# Stairs_v5.net
KiCad netlist of a schematic drawn in EAGLE
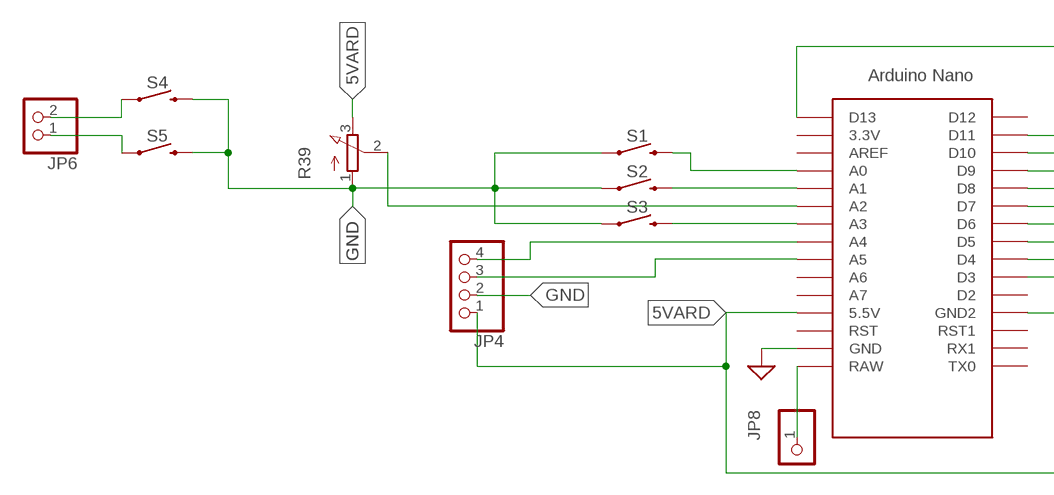
[diagram p0: schematic, sheet 1, part 1 of 2]
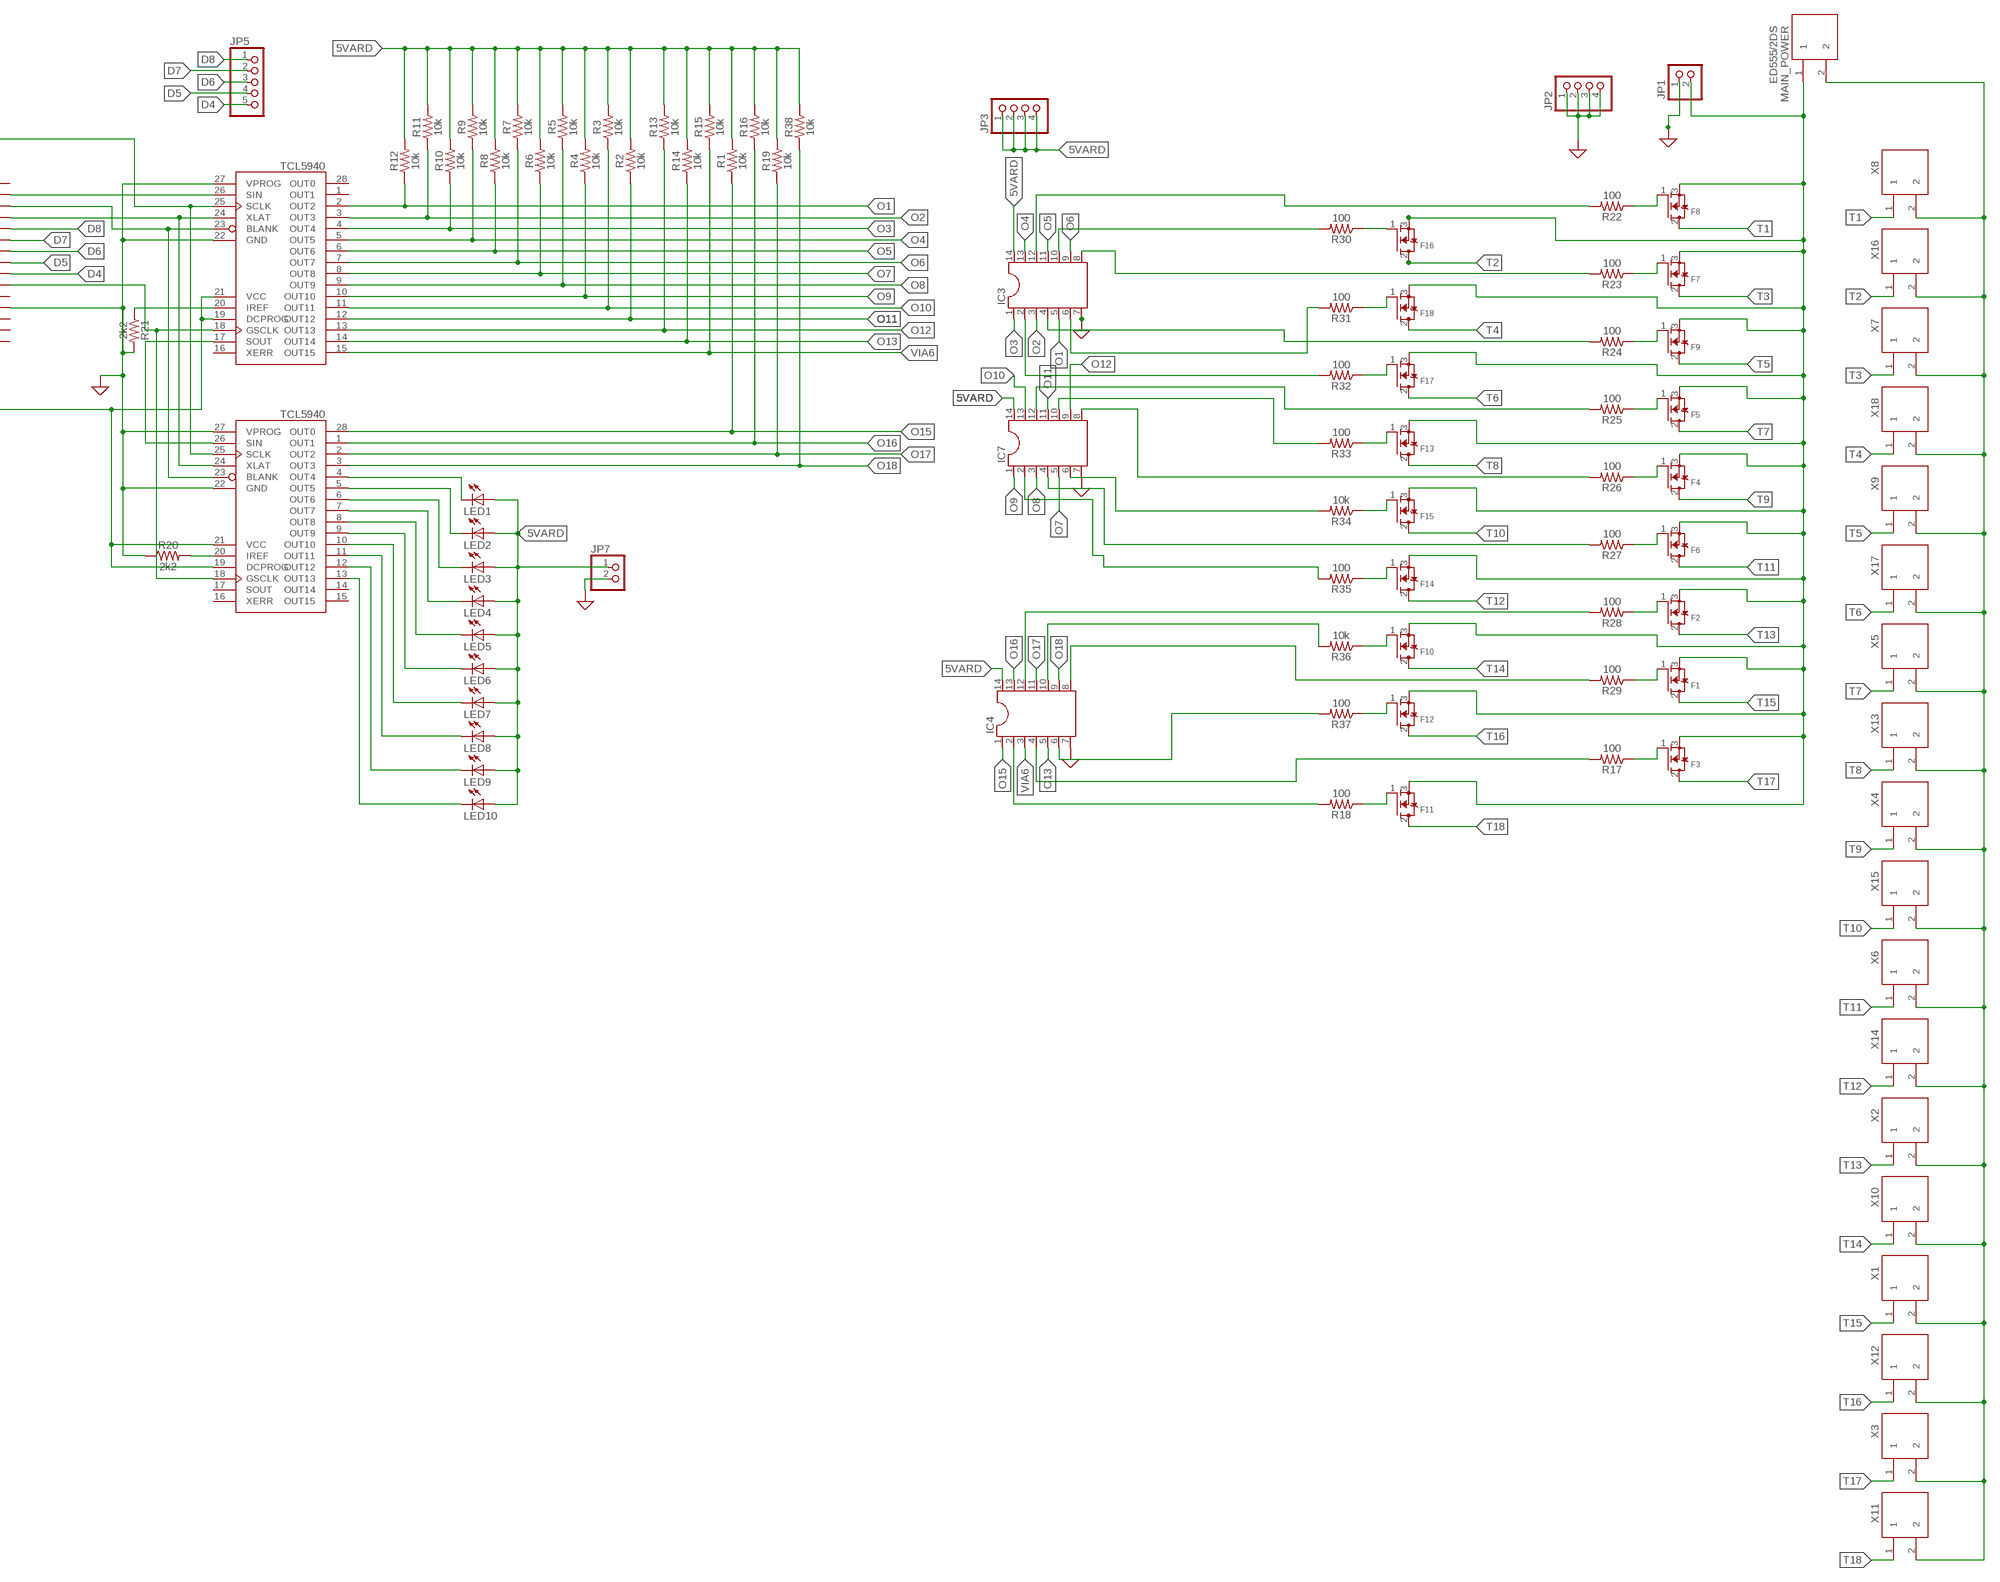
[diagram p1: schematic, sheet 1, part 2 of 2]

(export (version "E")
  (design (tool "Eeschema 10.0.6"))
  (components
    (comp (ref "F1")
      (value "MOSFET-NGDS_TO220V")
      (footprint "eagle-import:TO220V")
      (libsource (lib "eagle-import") (part "MOSFET-NGDS_TO220V"))
    )
    (comp (ref "F2")
      (value "MOSFET-NGDS_TO220V")
      (footprint "eagle-import:TO220V")
      (libsource (lib "eagle-import") (part "MOSFET-NGDS_TO220V"))
    )
    (comp (ref "F3")
      (value "MOSFET-NGDS_TO220V")
      (footprint "eagle-import:TO220V")
      (libsource (lib "eagle-import") (part "MOSFET-NGDS_TO220V"))
    )
    (comp (ref "F4")
      (value "MOSFET-NGDS_TO220V")
      (footprint "eagle-import:TO220V")
      (libsource (lib "eagle-import") (part "MOSFET-NGDS_TO220V"))
    )
    (comp (ref "F5")
      (value "MOSFET-NGDS_TO220V")
      (footprint "eagle-import:TO220V")
      (libsource (lib "eagle-import") (part "MOSFET-NGDS_TO220V"))
    )
    (comp (ref "F6")
      (value "MOSFET-NGDS_TO220V")
      (footprint "eagle-import:TO220V")
      (libsource (lib "eagle-import") (part "MOSFET-NGDS_TO220V"))
    )
    (comp (ref "F7")
      (value "MOSFET-NGDS_TO220V")
      (footprint "eagle-import:TO220V")
      (libsource (lib "eagle-import") (part "MOSFET-NGDS_TO220V"))
    )
    (comp (ref "F8")
      (value "MOSFET-NGDS_TO220V")
      (footprint "eagle-import:TO220V")
      (libsource (lib "eagle-import") (part "MOSFET-NGDS_TO220V"))
    )
    (comp (ref "F9")
      (value "MOSFET-NGDS_TO220V")
      (footprint "eagle-import:TO220V")
      (libsource (lib "eagle-import") (part "MOSFET-NGDS_TO220V"))
    )
    (comp (ref "F10")
      (value "MOSFET-NGDS_TO220V")
      (footprint "eagle-import:TO220V")
      (libsource (lib "eagle-import") (part "MOSFET-NGDS_TO220V"))
    )
    (comp (ref "F11")
      (value "MOSFET-NGDS_TO220V")
      (footprint "eagle-import:TO220V")
      (libsource (lib "eagle-import") (part "MOSFET-NGDS_TO220V"))
    )
    (comp (ref "F12")
      (value "MOSFET-NGDS_TO220V")
      (footprint "eagle-import:TO220V")
      (libsource (lib "eagle-import") (part "MOSFET-NGDS_TO220V"))
    )
    (comp (ref "F13")
      (value "MOSFET-NGDS_TO220V")
      (footprint "eagle-import:TO220V")
      (libsource (lib "eagle-import") (part "MOSFET-NGDS_TO220V"))
    )
    (comp (ref "F14")
      (value "MOSFET-NGDS_TO220V")
      (footprint "eagle-import:TO220V")
      (libsource (lib "eagle-import") (part "MOSFET-NGDS_TO220V"))
    )
    (comp (ref "F15")
      (value "MOSFET-NGDS_TO220V")
      (footprint "eagle-import:TO220V")
      (libsource (lib "eagle-import") (part "MOSFET-NGDS_TO220V"))
    )
    (comp (ref "F16")
      (value "MOSFET-NGDS_TO220V")
      (footprint "eagle-import:TO220V")
      (libsource (lib "eagle-import") (part "MOSFET-NGDS_TO220V"))
    )
    (comp (ref "F17")
      (value "MOSFET-NGDS_TO220V")
      (footprint "eagle-import:TO220V")
      (libsource (lib "eagle-import") (part "MOSFET-NGDS_TO220V"))
    )
    (comp (ref "F18")
      (value "MOSFET-NGDS_TO220V")
      (footprint "eagle-import:TO220V")
      (libsource (lib "eagle-import") (part "MOSFET-NGDS_TO220V"))
    )
    (comp (ref "IC1")
      (value "TCL5940")
      (footprint "eagle-import:DIP28")
      (libsource (lib "eagle-import") (part "TCL5940"))
    )
    (comp (ref "IC2")
      (value "TCL5940")
      (footprint "eagle-import:DIP28")
      (libsource (lib "eagle-import") (part "TCL5940"))
    )
    (comp (ref "IC3")
      (value "DIL14S")
      (footprint "eagle-import:SOCKET-14")
      (libsource (lib "eagle-import") (part "DIL14S"))
    )
    (comp (ref "IC4")
      (value "DIL14S")
      (footprint "eagle-import:SOCKET-14")
      (libsource (lib "eagle-import") (part "DIL14S"))
    )
    (comp (ref "IC7")
      (value "DIL14S")
      (footprint "eagle-import:SOCKET-14")
      (libsource (lib "eagle-import") (part "DIL14S"))
    )
    (comp (ref "JP1")
      (value "PINHD-1X2")
      (footprint "eagle-import:1X02")
      (libsource (lib "eagle-import") (part "PINHD-1X2"))
    )
    (comp (ref "JP2")
      (value "PINHD-1X4")
      (footprint "eagle-import:1X04")
      (libsource (lib "eagle-import") (part "PINHD-1X4"))
    )
    (comp (ref "JP3")
      (value "PINHD-1X4")
      (footprint "eagle-import:1X04")
      (libsource (lib "eagle-import") (part "PINHD-1X4"))
    )
    (comp (ref "JP4")
      (value "PINHD-1X4")
      (footprint "eagle-import:1X04")
      (libsource (lib "eagle-import") (part "PINHD-1X4"))
    )
    (comp (ref "JP5")
      (value "PINHD-1X5")
      (footprint "eagle-import:1X05")
      (libsource (lib "eagle-import") (part "PINHD-1X5"))
    )
    (comp (ref "JP6")
      (value "PINHD-1X2")
      (footprint "eagle-import:1X02")
      (libsource (lib "eagle-import") (part "PINHD-1X2"))
    )
    (comp (ref "JP7")
      (value "PINHD-1X2")
      (footprint "eagle-import:1X02")
      (libsource (lib "eagle-import") (part "PINHD-1X2"))
    )
    (comp (ref "JP8")
      (value "PINHD-1X1")
      (footprint "eagle-import:1X01")
      (libsource (lib "eagle-import") (part "PINHD-1X1"))
    )
    (comp (ref "LED1")
      (value "LEDSFH482")
      (footprint "eagle-import:SFH482")
      (libsource (lib "eagle-import") (part "LEDSFH482"))
    )
    (comp (ref "LED2")
      (value "LEDSFH482")
      (footprint "eagle-import:SFH482")
      (libsource (lib "eagle-import") (part "LEDSFH482"))
    )
    (comp (ref "LED3")
      (value "LEDSFH482")
      (footprint "eagle-import:SFH482")
      (libsource (lib "eagle-import") (part "LEDSFH482"))
    )
    (comp (ref "LED4")
      (value "LEDSFH482")
      (footprint "eagle-import:SFH482")
      (libsource (lib "eagle-import") (part "LEDSFH482"))
    )
    (comp (ref "LED5")
      (value "LEDSFH482")
      (footprint "eagle-import:SFH482")
      (libsource (lib "eagle-import") (part "LEDSFH482"))
    )
    (comp (ref "LED6")
      (value "LEDSFH482")
      (footprint "eagle-import:SFH482")
      (libsource (lib "eagle-import") (part "LEDSFH482"))
    )
    (comp (ref "LED7")
      (value "LEDSFH482")
      (footprint "eagle-import:SFH482")
      (libsource (lib "eagle-import") (part "LEDSFH482"))
    )
    (comp (ref "LED8")
      (value "LEDSFH482")
      (footprint "eagle-import:SFH482")
      (libsource (lib "eagle-import") (part "LEDSFH482"))
    )
    (comp (ref "LED9")
      (value "LEDSFH482")
      (footprint "eagle-import:SFH482")
      (libsource (lib "eagle-import") (part "LEDSFH482"))
    )
    (comp (ref "LED10")
      (value "LEDSFH482")
      (footprint "eagle-import:SFH482")
      (libsource (lib "eagle-import") (part "LEDSFH482"))
    )
    (comp (ref "MAIN_POWER")
      (value "ED555/2DS")
      (footprint "eagle-import:ED555_2DS")
      (libsource (lib "eagle-import") (part "ED555/2DS"))
    )
    (comp (ref "R1")
      (value "10k")
      (footprint "eagle-import:AXIAL-0.3-KIT")
      (libsource (lib "eagle-import") (part "10KOHM-HORIZ_KIT-1/4W-1%"))
    )
    (comp (ref "R2")
      (value "10k")
      (footprint "eagle-import:AXIAL-0.3-KIT")
      (libsource (lib "eagle-import") (part "10KOHM-HORIZ_KIT-1/4W-1%"))
    )
    (comp (ref "R3")
      (value "10k")
      (footprint "eagle-import:AXIAL-0.3-KIT")
      (libsource (lib "eagle-import") (part "10KOHM-HORIZ_KIT-1/4W-1%"))
    )
    (comp (ref "R4")
      (value "10k")
      (footprint "eagle-import:AXIAL-0.3-KIT")
      (libsource (lib "eagle-import") (part "10KOHM-HORIZ_KIT-1/4W-1%"))
    )
    (comp (ref "R5")
      (value "10k")
      (footprint "eagle-import:AXIAL-0.3-KIT")
      (libsource (lib "eagle-import") (part "10KOHM-HORIZ_KIT-1/4W-1%"))
    )
    (comp (ref "R6")
      (value "10k")
      (footprint "eagle-import:AXIAL-0.3-KIT")
      (libsource (lib "eagle-import") (part "10KOHM-HORIZ_KIT-1/4W-1%"))
    )
    (comp (ref "R7")
      (value "10k")
      (footprint "eagle-import:AXIAL-0.3-KIT")
      (libsource (lib "eagle-import") (part "10KOHM-HORIZ_KIT-1/4W-1%"))
    )
    (comp (ref "R8")
      (value "10k")
      (footprint "eagle-import:AXIAL-0.3-KIT")
      (libsource (lib "eagle-import") (part "10KOHM-HORIZ_KIT-1/4W-1%"))
    )
    (comp (ref "R9")
      (value "10k")
      (footprint "eagle-import:AXIAL-0.3-KIT")
      (libsource (lib "eagle-import") (part "10KOHM-HORIZ_KIT-1/4W-1%"))
    )
    (comp (ref "R10")
      (value "10k")
      (footprint "eagle-import:AXIAL-0.3-KIT")
      (libsource (lib "eagle-import") (part "10KOHM-HORIZ_KIT-1/4W-1%"))
    )
    (comp (ref "R11")
      (value "10k")
      (footprint "eagle-import:AXIAL-0.3-KIT")
      (libsource (lib "eagle-import") (part "10KOHM-HORIZ_KIT-1/4W-1%"))
    )
    (comp (ref "R12")
      (value "10k")
      (footprint "eagle-import:AXIAL-0.3-KIT")
      (libsource (lib "eagle-import") (part "10KOHM-HORIZ_KIT-1/4W-1%"))
    )
    (comp (ref "R13")
      (value "10k")
      (footprint "eagle-import:AXIAL-0.3-KIT")
      (libsource (lib "eagle-import") (part "10KOHM-HORIZ_KIT-1/4W-1%"))
    )
    (comp (ref "R14")
      (value "10k")
      (footprint "eagle-import:AXIAL-0.3-KIT")
      (libsource (lib "eagle-import") (part "10KOHM-HORIZ_KIT-1/4W-1%"))
    )
    (comp (ref "R15")
      (value "10k")
      (footprint "eagle-import:AXIAL-0.3-KIT")
      (libsource (lib "eagle-import") (part "10KOHM-HORIZ_KIT-1/4W-1%"))
    )
    (comp (ref "R16")
      (value "10k")
      (footprint "eagle-import:AXIAL-0.3-KIT")
      (libsource (lib "eagle-import") (part "10KOHM-HORIZ_KIT-1/4W-1%"))
    )
    (comp (ref "R17")
      (value "100")
      (footprint "eagle-import:AXIAL-0.3-KIT")
      (libsource (lib "eagle-import") (part "10KOHM-HORIZ_KIT-1/4W-1%"))
    )
    (comp (ref "R18")
      (value "100")
      (footprint "eagle-import:AXIAL-0.3-KIT")
      (libsource (lib "eagle-import") (part "10KOHM-HORIZ_KIT-1/4W-1%"))
    )
    (comp (ref "R19")
      (value "10k")
      (footprint "eagle-import:AXIAL-0.3-KIT")
      (libsource (lib "eagle-import") (part "10KOHM-HORIZ_KIT-1/4W-1%"))
    )
    (comp (ref "R20")
      (value "2k2")
      (footprint "eagle-import:AXIAL-0.3-KIT")
      (libsource (lib "eagle-import") (part "10KOHM-HORIZ_KIT-1/4W-1%"))
    )
    (comp (ref "R21")
      (value "2k2")
      (footprint "eagle-import:AXIAL-0.3-KIT")
      (libsource (lib "eagle-import") (part "10KOHM-HORIZ_KIT-1/4W-1%"))
    )
    (comp (ref "R22")
      (value "100")
      (footprint "eagle-import:AXIAL-0.3-KIT")
      (libsource (lib "eagle-import") (part "10KOHM-HORIZ_KIT-1/4W-1%"))
    )
    (comp (ref "R23")
      (value "100")
      (footprint "eagle-import:AXIAL-0.3-KIT")
      (libsource (lib "eagle-import") (part "10KOHM-HORIZ_KIT-1/4W-1%"))
    )
    (comp (ref "R24")
      (value "100")
      (footprint "eagle-import:AXIAL-0.3-KIT")
      (libsource (lib "eagle-import") (part "10KOHM-HORIZ_KIT-1/4W-1%"))
    )
    (comp (ref "R25")
      (value "100")
      (footprint "eagle-import:AXIAL-0.3-KIT")
      (libsource (lib "eagle-import") (part "10KOHM-HORIZ_KIT-1/4W-1%"))
    )
    (comp (ref "R26")
      (value "100")
      (footprint "eagle-import:AXIAL-0.3-KIT")
      (libsource (lib "eagle-import") (part "10KOHM-HORIZ_KIT-1/4W-1%"))
    )
    (comp (ref "R27")
      (value "100")
      (footprint "eagle-import:AXIAL-0.3-KIT")
      (libsource (lib "eagle-import") (part "10KOHM-HORIZ_KIT-1/4W-1%"))
    )
    (comp (ref "R28")
      (value "100")
      (footprint "eagle-import:AXIAL-0.3-KIT")
      (libsource (lib "eagle-import") (part "10KOHM-HORIZ_KIT-1/4W-1%"))
    )
    (comp (ref "R29")
      (value "100")
      (footprint "eagle-import:AXIAL-0.3-KIT")
      (libsource (lib "eagle-import") (part "10KOHM-HORIZ_KIT-1/4W-1%"))
    )
    (comp (ref "R30")
      (value "100")
      (footprint "eagle-import:AXIAL-0.3-KIT")
      (libsource (lib "eagle-import") (part "10KOHM-HORIZ_KIT-1/4W-1%"))
    )
    (comp (ref "R31")
      (value "100")
      (footprint "eagle-import:AXIAL-0.3-KIT")
      (libsource (lib "eagle-import") (part "10KOHM-HORIZ_KIT-1/4W-1%"))
    )
    (comp (ref "R32")
      (value "100")
      (footprint "eagle-import:AXIAL-0.3-KIT")
      (libsource (lib "eagle-import") (part "10KOHM-HORIZ_KIT-1/4W-1%"))
    )
    (comp (ref "R33")
      (value "100")
      (footprint "eagle-import:AXIAL-0.3-KIT")
      (libsource (lib "eagle-import") (part "10KOHM-HORIZ_KIT-1/4W-1%"))
    )
    (comp (ref "R34")
      (value "10k")
      (footprint "eagle-import:AXIAL-0.3-KIT")
      (libsource (lib "eagle-import") (part "10KOHM-HORIZ_KIT-1/4W-1%"))
    )
    (comp (ref "R35")
      (value "100")
      (footprint "eagle-import:AXIAL-0.3-KIT")
      (libsource (lib "eagle-import") (part "10KOHM-HORIZ_KIT-1/4W-1%"))
    )
    (comp (ref "R36")
      (value "10k")
      (footprint "eagle-import:AXIAL-0.3-KIT")
      (libsource (lib "eagle-import") (part "10KOHM-HORIZ_KIT-1/4W-1%"))
    )
    (comp (ref "R37")
      (value "100")
      (footprint "eagle-import:AXIAL-0.3-KIT")
      (libsource (lib "eagle-import") (part "10KOHM-HORIZ_KIT-1/4W-1%"))
    )
    (comp (ref "R38")
      (value "10k")
      (footprint "eagle-import:AXIAL-0.3-KIT")
      (libsource (lib "eagle-import") (part "10KOHM-HORIZ_KIT-1/4W-1%"))
    )
    (comp (ref "R39")
      (value "3RP/1610N")
      (footprint "eagle-import:3RP_1610N")
      (libsource (lib "eagle-import") (part "3RP/1610N"))
    )
    (comp (ref "S1")
      (value "MOMENTARY-SWITCH-SPST-PTH-6.0MM")
      (footprint "eagle-import:TACTILE_SWITCH_PTH_6.0MM")
      (libsource (lib "eagle-import") (part "MOMENTARY-SWITCH-SPST-PTH-6.0MM"))
    )
    (comp (ref "S2")
      (value "MOMENTARY-SWITCH-SPST-PTH-6.0MM")
      (footprint "eagle-import:TACTILE_SWITCH_PTH_6.0MM")
      (libsource (lib "eagle-import") (part "MOMENTARY-SWITCH-SPST-PTH-6.0MM"))
    )
    (comp (ref "S3")
      (value "MOMENTARY-SWITCH-SPST-PTH-6.0MM")
      (footprint "eagle-import:TACTILE_SWITCH_PTH_6.0MM")
      (libsource (lib "eagle-import") (part "MOMENTARY-SWITCH-SPST-PTH-6.0MM"))
    )
    (comp (ref "S4")
      (value "MOMENTARY-SWITCH-SPST-PTH-6.0MM")
      (footprint "eagle-import:TACTILE_SWITCH_PTH_6.0MM")
      (libsource (lib "eagle-import") (part "MOMENTARY-SWITCH-SPST-PTH-6.0MM"))
    )
    (comp (ref "S5")
      (value "MOMENTARY-SWITCH-SPST-PTH-6.0MM")
      (footprint "eagle-import:TACTILE_SWITCH_PTH_6.0MM")
      (libsource (lib "eagle-import") (part "MOMENTARY-SWITCH-SPST-PTH-6.0MM"))
    )
    (comp (ref "U$1")
      (value "NANO")
      (footprint "eagle-import:NANO")
      (libsource (lib "eagle-import") (part "NANO"))
    )
    (comp (ref "X1")
      (value "ED555/2DS")
      (footprint "eagle-import:ED555_2DS")
      (libsource (lib "eagle-import") (part "ED555/2DS"))
    )
    (comp (ref "X2")
      (value "ED555/2DS")
      (footprint "eagle-import:ED555_2DS")
      (libsource (lib "eagle-import") (part "ED555/2DS"))
    )
    (comp (ref "X3")
      (value "ED555/2DS")
      (footprint "eagle-import:ED555_2DS")
      (libsource (lib "eagle-import") (part "ED555/2DS"))
    )
    (comp (ref "X4")
      (value "ED555/2DS")
      (footprint "eagle-import:ED555_2DS")
      (libsource (lib "eagle-import") (part "ED555/2DS"))
    )
    (comp (ref "X5")
      (value "ED555/2DS")
      (footprint "eagle-import:ED555_2DS")
      (libsource (lib "eagle-import") (part "ED555/2DS"))
    )
    (comp (ref "X6")
      (value "ED555/2DS")
      (footprint "eagle-import:ED555_2DS")
      (libsource (lib "eagle-import") (part "ED555/2DS"))
    )
    (comp (ref "X7")
      (value "ED555/2DS")
      (footprint "eagle-import:ED555_2DS")
      (libsource (lib "eagle-import") (part "ED555/2DS"))
    )
    (comp (ref "X8")
      (value "ED555/2DS")
      (footprint "eagle-import:ED555_2DS")
      (libsource (lib "eagle-import") (part "ED555/2DS"))
    )
    (comp (ref "X9")
      (value "ED555/2DS")
      (footprint "eagle-import:ED555_2DS")
      (libsource (lib "eagle-import") (part "ED555/2DS"))
    )
    (comp (ref "X10")
      (value "ED555/2DS")
      (footprint "eagle-import:ED555_2DS")
      (libsource (lib "eagle-import") (part "ED555/2DS"))
    )
    (comp (ref "X11")
      (value "ED555/2DS")
      (footprint "eagle-import:ED555_2DS")
      (libsource (lib "eagle-import") (part "ED555/2DS"))
    )
    (comp (ref "X12")
      (value "ED555/2DS")
      (footprint "eagle-import:ED555_2DS")
      (libsource (lib "eagle-import") (part "ED555/2DS"))
    )
    (comp (ref "X13")
      (value "ED555/2DS")
      (footprint "eagle-import:ED555_2DS")
      (libsource (lib "eagle-import") (part "ED555/2DS"))
    )
    (comp (ref "X14")
      (value "ED555/2DS")
      (footprint "eagle-import:ED555_2DS")
      (libsource (lib "eagle-import") (part "ED555/2DS"))
    )
    (comp (ref "X15")
      (value "ED555/2DS")
      (footprint "eagle-import:ED555_2DS")
      (libsource (lib "eagle-import") (part "ED555/2DS"))
    )
    (comp (ref "X16")
      (value "ED555/2DS")
      (footprint "eagle-import:ED555_2DS")
      (libsource (lib "eagle-import") (part "ED555/2DS"))
    )
    (comp (ref "X17")
      (value "ED555/2DS")
      (footprint "eagle-import:ED555_2DS")
      (libsource (lib "eagle-import") (part "ED555/2DS"))
    )
    (comp (ref "X18")
      (value "ED555/2DS")
      (footprint "eagle-import:ED555_2DS")
      (libsource (lib "eagle-import") (part "ED555/2DS"))
    )
  )
  (nets
    (net (code "1") (name "5VARD") (class "Default")
      (node (ref "IC1") (pin "19") (pinfunction "DCPROG_19") (pintype "input"))
      (node (ref "IC1") (pin "21") (pinfunction "VCC_21") (pintype "power_in"))
      (node (ref "IC2") (pin "19") (pinfunction "DCPROG_19") (pintype "input"))
      (node (ref "IC2") (pin "21") (pinfunction "VCC_21") (pintype "power_in"))
      (node (ref "IC3") (pin "14") (pinfunction "14_14") (pintype "passive"))
      (node (ref "IC4") (pin "14") (pinfunction "14_14") (pintype "passive"))
      (node (ref "IC7") (pin "14") (pinfunction "14_14") (pintype "passive"))
      (node (ref "JP3") (pin "1") (pinfunction "1_1") (pintype "passive"))
      (node (ref "JP3") (pin "2") (pinfunction "2_2") (pintype "passive"))
      (node (ref "JP3") (pin "3") (pinfunction "3_3") (pintype "passive"))
      (node (ref "JP3") (pin "4") (pinfunction "4_4") (pintype "passive"))
      (node (ref "JP4") (pin "1") (pinfunction "1_1") (pintype "passive"))
      (node (ref "JP7") (pin "1") (pinfunction "1_1") (pintype "passive"))
      (node (ref "LED1") (pin "A") (pinfunction "A_A") (pintype "passive"))
      (node (ref "LED10") (pin "A") (pinfunction "A_A") (pintype "passive"))
      (node (ref "LED2") (pin "A") (pinfunction "A_A") (pintype "passive"))
      (node (ref "LED3") (pin "A") (pinfunction "A_A") (pintype "passive"))
      (node (ref "LED4") (pin "A") (pinfunction "A_A") (pintype "passive"))
      (node (ref "LED5") (pin "A") (pinfunction "A_A") (pintype "passive"))
      (node (ref "LED6") (pin "A") (pinfunction "A_A") (pintype "passive"))
      (node (ref "LED7") (pin "A") (pinfunction "A_A") (pintype "passive"))
      (node (ref "LED8") (pin "A") (pinfunction "A_A") (pintype "passive"))
      (node (ref "LED9") (pin "A") (pinfunction "A_A") (pintype "passive"))
      (node (ref "R1") (pin "P$2") (pinfunction "2_P$2") (pintype "passive"))
      (node (ref "R10") (pin "P$2") (pinfunction "2_P$2") (pintype "passive"))
      (node (ref "R11") (pin "P$2") (pinfunction "2_P$2") (pintype "passive"))
      (node (ref "R12") (pin "P$2") (pinfunction "2_P$2") (pintype "passive"))
      (node (ref "R13") (pin "P$2") (pinfunction "2_P$2") (pintype "passive"))
      (node (ref "R14") (pin "P$2") (pinfunction "2_P$2") (pintype "passive"))
      (node (ref "R15") (pin "P$2") (pinfunction "2_P$2") (pintype "passive"))
      (node (ref "R16") (pin "P$2") (pinfunction "2_P$2") (pintype "passive"))
      (node (ref "R19") (pin "P$2") (pinfunction "2_P$2") (pintype "passive"))
      (node (ref "R2") (pin "P$2") (pinfunction "2_P$2") (pintype "passive"))
      (node (ref "R3") (pin "P$2") (pinfunction "2_P$2") (pintype "passive"))
      (node (ref "R38") (pin "P$2") (pinfunction "2_P$2") (pintype "passive"))
      (node (ref "R39") (pin "3") (pinfunction "E_3") (pintype "passive"))
      (node (ref "R4") (pin "P$2") (pinfunction "2_P$2") (pintype "passive"))
      (node (ref "R5") (pin "P$2") (pinfunction "2_P$2") (pintype "passive"))
      (node (ref "R6") (pin "P$2") (pinfunction "2_P$2") (pintype "passive"))
      (node (ref "R7") (pin "P$2") (pinfunction "2_P$2") (pintype "passive"))
      (node (ref "R8") (pin "P$2") (pinfunction "2_P$2") (pintype "passive"))
      (node (ref "R9") (pin "P$2") (pinfunction "2_P$2") (pintype "passive"))
      (node (ref "U$1") (pin "5V") (pinfunction "5.5V_5V") (pintype "bidirectional"))
    )
    (net (code "2") (name "D4") (class "Default")
      (node (ref "JP5") (pin "5") (pinfunction "5_5") (pintype "passive"))
      (node (ref "U$1") (pin "D4") (pinfunction "D4_D4") (pintype "bidirectional"))
    )
    (net (code "3") (name "D5") (class "Default")
      (node (ref "JP5") (pin "4") (pinfunction "4_4") (pintype "passive"))
      (node (ref "U$1") (pin "D5") (pinfunction "D5_D5") (pintype "bidirectional"))
    )
    (net (code "4") (name "D6") (class "Default")
      (node (ref "JP5") (pin "3") (pinfunction "3_3") (pintype "passive"))
      (node (ref "U$1") (pin "D6") (pinfunction "D6_D6") (pintype "bidirectional"))
    )
    (net (code "5") (name "D7") (class "Default")
      (node (ref "JP5") (pin "2") (pinfunction "2_2") (pintype "passive"))
      (node (ref "U$1") (pin "D7") (pinfunction "D7_D7") (pintype "bidirectional"))
    )
    (net (code "6") (name "D8") (class "Default")
      (node (ref "JP5") (pin "1") (pinfunction "1_1") (pintype "passive"))
      (node (ref "U$1") (pin "D8") (pinfunction "D8_D8") (pintype "bidirectional"))
    )
    (net (code "7") (name "GND") (class "Default")
      (node (ref "IC1") (pin "22") (pinfunction "GND_22") (pintype "power_in"))
      (node (ref "IC1") (pin "27") (pinfunction "VPROG_27") (pintype "bidirectional"))
      (node (ref "IC2") (pin "22") (pinfunction "GND_22") (pintype "power_in"))
      (node (ref "IC2") (pin "27") (pinfunction "VPROG_27") (pintype "bidirectional"))
      (node (ref "IC3") (pin "7") (pinfunction "7_7") (pintype "passive"))
      (node (ref "IC4") (pin "7") (pinfunction "7_7") (pintype "passive"))
      (node (ref "IC7") (pin "7") (pinfunction "7_7") (pintype "passive"))
      (node (ref "JP1") (pin "1") (pinfunction "1_1") (pintype "passive"))
      (node (ref "JP2") (pin "1") (pinfunction "1_1") (pintype "passive"))
      (node (ref "JP2") (pin "2") (pinfunction "2_2") (pintype "passive"))
      (node (ref "JP2") (pin "3") (pinfunction "3_3") (pintype "passive"))
      (node (ref "JP2") (pin "4") (pinfunction "4_4") (pintype "passive"))
      (node (ref "JP4") (pin "2") (pinfunction "2_2") (pintype "passive"))
      (node (ref "JP7") (pin "2") (pinfunction "2_2") (pintype "passive"))
      (node (ref "R20") (pin "P$1") (pinfunction "1_P$1") (pintype "passive"))
      (node (ref "R21") (pin "P$2") (pinfunction "2_P$2") (pintype "passive"))
      (node (ref "R39") (pin "1") (pinfunction "A_1") (pintype "passive"))
      (node (ref "S1") (pin "1") (pinfunction "1_1") (pintype "passive"))
      (node (ref "S2") (pin "1") (pinfunction "1_1") (pintype "passive"))
      (node (ref "S3") (pin "1") (pinfunction "1_1") (pintype "passive"))
      (node (ref "S4") (pin "3") (pinfunction "2_3") (pintype "passive"))
      (node (ref "S5") (pin "3") (pinfunction "2_3") (pintype "passive"))
      (node (ref "U$1") (pin "GND") (pinfunction "GND_GND") (pintype "bidirectional"))
      (node (ref "U$1") (pin "GND1") (pinfunction "GND2_GND1") (pintype "bidirectional"))
    )
    (net (code "8") (name "Net-(F1-G)") (class "Default")
      (node (ref "F1") (pin "1") (pinfunction "G_1") (pintype "bidirectional"))
      (node (ref "R29") (pin "P$1") (pinfunction "1_P$1") (pintype "passive"))
    )
    (net (code "9") (name "Net-(F1-S)") (class "Default")
      (node (ref "F1") (pin "3") (pinfunction "S_3") (pintype "bidirectional"))
      (node (ref "F10") (pin "3") (pinfunction "S_3") (pintype "bidirectional"))
      (node (ref "F11") (pin "3") (pinfunction "S_3") (pintype "bidirectional"))
      (node (ref "F12") (pin "3") (pinfunction "S_3") (pintype "bidirectional"))
      (node (ref "F13") (pin "3") (pinfunction "S_3") (pintype "bidirectional"))
      (node (ref "F14") (pin "3") (pinfunction "S_3") (pintype "bidirectional"))
      (node (ref "F15") (pin "3") (pinfunction "S_3") (pintype "bidirectional"))
      (node (ref "F16") (pin "3") (pinfunction "S_3") (pintype "bidirectional"))
      (node (ref "F17") (pin "3") (pinfunction "S_3") (pintype "bidirectional"))
      (node (ref "F18") (pin "3") (pinfunction "S_3") (pintype "bidirectional"))
      (node (ref "F2") (pin "3") (pinfunction "S_3") (pintype "bidirectional"))
      (node (ref "F3") (pin "3") (pinfunction "S_3") (pintype "bidirectional"))
      (node (ref "F4") (pin "3") (pinfunction "S_3") (pintype "bidirectional"))
      (node (ref "F5") (pin "3") (pinfunction "S_3") (pintype "bidirectional"))
      (node (ref "F6") (pin "3") (pinfunction "S_3") (pintype "bidirectional"))
      (node (ref "F7") (pin "3") (pinfunction "S_3") (pintype "bidirectional"))
      (node (ref "F8") (pin "3") (pinfunction "S_3") (pintype "bidirectional"))
      (node (ref "F9") (pin "3") (pinfunction "S_3") (pintype "bidirectional"))
      (node (ref "JP1") (pin "2") (pinfunction "2_2") (pintype "passive"))
      (node (ref "MAIN_POWER") (pin "1") (pinfunction "1_1") (pintype "bidirectional"))
    )
    (net (code "10") (name "Net-(F2-G)") (class "Default")
      (node (ref "F2") (pin "1") (pinfunction "G_1") (pintype "bidirectional"))
      (node (ref "R28") (pin "P$1") (pinfunction "1_P$1") (pintype "passive"))
    )
    (net (code "11") (name "Net-(F3-G)") (class "Default")
      (node (ref "F3") (pin "1") (pinfunction "G_1") (pintype "bidirectional"))
      (node (ref "R17") (pin "P$1") (pinfunction "1_P$1") (pintype "passive"))
    )
    (net (code "12") (name "Net-(F4-G)") (class "Default")
      (node (ref "F4") (pin "1") (pinfunction "G_1") (pintype "bidirectional"))
      (node (ref "R26") (pin "P$1") (pinfunction "1_P$1") (pintype "passive"))
    )
    (net (code "13") (name "Net-(F5-G)") (class "Default")
      (node (ref "F5") (pin "1") (pinfunction "G_1") (pintype "bidirectional"))
      (node (ref "R25") (pin "P$1") (pinfunction "1_P$1") (pintype "passive"))
    )
    (net (code "14") (name "Net-(F6-G)") (class "Default")
      (node (ref "F6") (pin "1") (pinfunction "G_1") (pintype "bidirectional"))
      (node (ref "R27") (pin "P$1") (pinfunction "1_P$1") (pintype "passive"))
    )
    (net (code "15") (name "Net-(F7-G)") (class "Default")
      (node (ref "F7") (pin "1") (pinfunction "G_1") (pintype "bidirectional"))
      (node (ref "R23") (pin "P$1") (pinfunction "1_P$1") (pintype "passive"))
    )
    (net (code "16") (name "Net-(F8-G)") (class "Default")
      (node (ref "F8") (pin "1") (pinfunction "G_1") (pintype "bidirectional"))
      (node (ref "R22") (pin "P$1") (pinfunction "1_P$1") (pintype "passive"))
    )
    (net (code "17") (name "Net-(F9-G)") (class "Default")
      (node (ref "F9") (pin "1") (pinfunction "G_1") (pintype "bidirectional"))
      (node (ref "R24") (pin "P$1") (pinfunction "1_P$1") (pintype "passive"))
    )
    (net (code "18") (name "Net-(F10-G)") (class "Default")
      (node (ref "F10") (pin "1") (pinfunction "G_1") (pintype "bidirectional"))
      (node (ref "R36") (pin "P$1") (pinfunction "1_P$1") (pintype "passive"))
    )
    (net (code "19") (name "Net-(F11-G)") (class "Default")
      (node (ref "F11") (pin "1") (pinfunction "G_1") (pintype "bidirectional"))
      (node (ref "R18") (pin "P$1") (pinfunction "1_P$1") (pintype "passive"))
    )
    (net (code "20") (name "Net-(F12-G)") (class "Default")
      (node (ref "F12") (pin "1") (pinfunction "G_1") (pintype "bidirectional"))
      (node (ref "R37") (pin "P$1") (pinfunction "1_P$1") (pintype "passive"))
    )
    (net (code "21") (name "Net-(F13-G)") (class "Default")
      (node (ref "F13") (pin "1") (pinfunction "G_1") (pintype "bidirectional"))
      (node (ref "R33") (pin "P$1") (pinfunction "1_P$1") (pintype "passive"))
    )
    (net (code "22") (name "Net-(F14-G)") (class "Default")
      (node (ref "F14") (pin "1") (pinfunction "G_1") (pintype "bidirectional"))
      (node (ref "R35") (pin "P$1") (pinfunction "1_P$1") (pintype "passive"))
    )
    (net (code "23") (name "Net-(F15-G)") (class "Default")
      (node (ref "F15") (pin "1") (pinfunction "G_1") (pintype "bidirectional"))
      (node (ref "R34") (pin "P$1") (pinfunction "1_P$1") (pintype "passive"))
    )
    (net (code "24") (name "Net-(F16-G)") (class "Default")
      (node (ref "F16") (pin "1") (pinfunction "G_1") (pintype "bidirectional"))
      (node (ref "R30") (pin "P$1") (pinfunction "1_P$1") (pintype "passive"))
    )
    (net (code "25") (name "Net-(F17-G)") (class "Default")
      (node (ref "F17") (pin "1") (pinfunction "G_1") (pintype "bidirectional"))
      (node (ref "R32") (pin "P$1") (pinfunction "1_P$1") (pintype "passive"))
    )
    (net (code "26") (name "Net-(F18-G)") (class "Default")
      (node (ref "F18") (pin "1") (pinfunction "G_1") (pintype "bidirectional"))
      (node (ref "R31") (pin "P$1") (pinfunction "1_P$1") (pintype "passive"))
    )
    (net (code "27") (name "Net-(IC1-BLANK)") (class "Default")
      (node (ref "IC1") (pin "23") (pinfunction "BLANK_23") (pintype "input"))
      (node (ref "IC2") (pin "23") (pinfunction "BLANK_23") (pintype "input"))
      (node (ref "U$1") (pin "D10") (pinfunction "D10_D10") (pintype "bidirectional"))
    )
    (net (code "28") (name "Net-(IC1-GSCLK)") (class "Default")
      (node (ref "IC1") (pin "18") (pinfunction "GSCLK_18") (pintype "input"))
      (node (ref "IC2") (pin "18") (pinfunction "GSCLK_18") (pintype "input"))
      (node (ref "U$1") (pin "D3") (pinfunction "D3_D3") (pintype "bidirectional"))
    )
    (net (code "29") (name "Net-(IC1-IREF)") (class "Default")
      (node (ref "IC1") (pin "20") (pinfunction "IREF_20") (pintype "input"))
      (node (ref "R21") (pin "P$1") (pinfunction "1_P$1") (pintype "passive"))
    )
    (net (code "30") (name "Net-(IC1-SCLK)") (class "Default")
      (node (ref "IC1") (pin "25") (pinfunction "SCLK_25") (pintype "input"))
      (node (ref "IC2") (pin "25") (pinfunction "SCLK_25") (pintype "input"))
      (node (ref "U$1") (pin "D13") (pinfunction "D13_D13") (pintype "bidirectional"))
    )
    (net (code "31") (name "Net-(IC1-SIN)") (class "Default")
      (node (ref "IC1") (pin "26") (pinfunction "SIN_26") (pintype "input"))
      (node (ref "U$1") (pin "D11") (pinfunction "D11_D11") (pintype "bidirectional"))
    )
    (net (code "32") (name "Net-(IC1-SOUT)") (class "Default")
      (node (ref "IC1") (pin "17") (pinfunction "SOUT_17") (pintype "output"))
      (node (ref "IC2") (pin "26") (pinfunction "SIN_26") (pintype "input"))
    )
    (net (code "33") (name "Net-(IC1-XLAT)") (class "Default")
      (node (ref "IC1") (pin "24") (pinfunction "XLAT_24") (pintype "input"))
      (node (ref "IC2") (pin "24") (pinfunction "XLAT_24") (pintype "input"))
      (node (ref "U$1") (pin "D9") (pinfunction "D9_D9") (pintype "bidirectional"))
    )
    (net (code "34") (name "Net-(IC2-IREF)") (class "Default")
      (node (ref "IC2") (pin "20") (pinfunction "IREF_20") (pintype "input"))
      (node (ref "R20") (pin "P$2") (pinfunction "2_P$2") (pintype "passive"))
    )
    (net (code "35") (name "Net-(IC2-OUT4)") (class "Default")
      (node (ref "IC2") (pin "4") (pinfunction "OUT4_4") (pintype "output"))
      (node (ref "LED1") (pin "K") (pinfunction "C_K") (pintype "passive"))
    )
    (net (code "36") (name "Net-(IC2-OUT5)") (class "Default")
      (node (ref "IC2") (pin "5") (pinfunction "OUT5_5") (pintype "output"))
      (node (ref "LED2") (pin "K") (pinfunction "C_K") (pintype "passive"))
    )
    (net (code "37") (name "Net-(IC2-OUT6)") (class "Default")
      (node (ref "IC2") (pin "6") (pinfunction "OUT6_6") (pintype "output"))
      (node (ref "LED3") (pin "K") (pinfunction "C_K") (pintype "passive"))
    )
    (net (code "38") (name "Net-(IC2-OUT7)") (class "Default")
      (node (ref "IC2") (pin "7") (pinfunction "OUT7_7") (pintype "output"))
      (node (ref "LED4") (pin "K") (pinfunction "C_K") (pintype "passive"))
    )
    (net (code "39") (name "Net-(IC2-OUT8)") (class "Default")
      (node (ref "IC2") (pin "8") (pinfunction "OUT8_8") (pintype "output"))
      (node (ref "LED5") (pin "K") (pinfunction "C_K") (pintype "passive"))
    )
    (net (code "40") (name "Net-(IC2-OUT9)") (class "Default")
      (node (ref "IC2") (pin "9") (pinfunction "OUT9_9") (pintype "output"))
      (node (ref "LED6") (pin "K") (pinfunction "C_K") (pintype "passive"))
    )
    (net (code "41") (name "Net-(IC2-OUT10)") (class "Default")
      (node (ref "IC2") (pin "10") (pinfunction "OUT10_10") (pintype "output"))
      (node (ref "LED7") (pin "K") (pinfunction "C_K") (pintype "passive"))
    )
    (net (code "42") (name "Net-(IC2-OUT11)") (class "Default")
      (node (ref "IC2") (pin "11") (pinfunction "OUT11_11") (pintype "output"))
      (node (ref "LED8") (pin "K") (pinfunction "C_K") (pintype "passive"))
    )
    (net (code "43") (name "Net-(IC2-OUT12)") (class "Default")
      (node (ref "IC2") (pin "12") (pinfunction "OUT12_12") (pintype "output"))
      (node (ref "LED9") (pin "K") (pinfunction "C_K") (pintype "passive"))
    )
    (net (code "44") (name "Net-(IC2-OUT13)") (class "Default")
      (node (ref "IC2") (pin "13") (pinfunction "OUT13_13") (pintype "output"))
      (node (ref "LED10") (pin "K") (pinfunction "C_K") (pintype "passive"))
    )
    (net (code "45") (name "Net-(JP4-Pad3)") (class "Default")
      (node (ref "JP4") (pin "3") (pinfunction "3_3") (pintype "passive"))
      (node (ref "U$1") (pin "A5") (pinfunction "A5_A5") (pintype "bidirectional"))
    )
    (net (code "46") (name "Net-(JP4-Pad4)") (class "Default")
      (node (ref "JP4") (pin "4") (pinfunction "4_4") (pintype "passive"))
      (node (ref "U$1") (pin "A4") (pinfunction "A4_A4") (pintype "bidirectional"))
    )
    (net (code "47") (name "Net-(JP6-Pad1)") (class "Default")
      (node (ref "JP6") (pin "1") (pinfunction "1_1") (pintype "passive"))
      (node (ref "S5") (pin "1") (pinfunction "1_1") (pintype "passive"))
    )
    (net (code "48") (name "Net-(JP6-Pad2)") (class "Default")
      (node (ref "JP6") (pin "2") (pinfunction "2_2") (pintype "passive"))
      (node (ref "S4") (pin "1") (pinfunction "1_1") (pintype "passive"))
    )
    (net (code "49") (name "Net-(JP8-Pad1)") (class "Default")
      (node (ref "JP8") (pin "1") (pinfunction "1_1") (pintype "passive"))
      (node (ref "U$1") (pin "RAW") (pinfunction "RAW_RAW") (pintype "bidirectional"))
    )
    (net (code "50") (name "Net-(MAIN_POWER-Pad2)") (class "Default")
      (node (ref "MAIN_POWER") (pin "2") (pinfunction "2_2") (pintype "bidirectional"))
      (node (ref "X1") (pin "2") (pinfunction "2_2") (pintype "bidirectional"))
      (node (ref "X10") (pin "2") (pinfunction "2_2") (pintype "bidirectional"))
      (node (ref "X11") (pin "2") (pinfunction "2_2") (pintype "bidirectional"))
      (node (ref "X12") (pin "2") (pinfunction "2_2") (pintype "bidirectional"))
      (node (ref "X13") (pin "2") (pinfunction "2_2") (pintype "bidirectional"))
      (node (ref "X14") (pin "2") (pinfunction "2_2") (pintype "bidirectional"))
      (node (ref "X15") (pin "2") (pinfunction "2_2") (pintype "bidirectional"))
      (node (ref "X16") (pin "2") (pinfunction "2_2") (pintype "bidirectional"))
      (node (ref "X17") (pin "2") (pinfunction "2_2") (pintype "bidirectional"))
      (node (ref "X18") (pin "2") (pinfunction "2_2") (pintype "bidirectional"))
      (node (ref "X2") (pin "2") (pinfunction "2_2") (pintype "bidirectional"))
      (node (ref "X3") (pin "2") (pinfunction "2_2") (pintype "bidirectional"))
      (node (ref "X4") (pin "2") (pinfunction "2_2") (pintype "bidirectional"))
      (node (ref "X5") (pin "2") (pinfunction "2_2") (pintype "bidirectional"))
      (node (ref "X6") (pin "2") (pinfunction "2_2") (pintype "bidirectional"))
      (node (ref "X7") (pin "2") (pinfunction "2_2") (pintype "bidirectional"))
      (node (ref "X8") (pin "2") (pinfunction "2_2") (pintype "bidirectional"))
      (node (ref "X9") (pin "2") (pinfunction "2_2") (pintype "bidirectional"))
    )
    (net (code "51") (name "Net-(R17-2)") (class "Default")
      (node (ref "IC4") (pin "4") (pinfunction "4_4") (pintype "passive"))
      (node (ref "R17") (pin "P$2") (pinfunction "2_P$2") (pintype "passive"))
    )
    (net (code "52") (name "Net-(R18-2)") (class "Default")
      (node (ref "IC4") (pin "2") (pinfunction "2_2") (pintype "passive"))
      (node (ref "R18") (pin "P$2") (pinfunction "2_P$2") (pintype "passive"))
    )
    (net (code "53") (name "Net-(R22-2)") (class "Default")
      (node (ref "IC3") (pin "12") (pinfunction "12_12") (pintype "passive"))
      (node (ref "R22") (pin "P$2") (pinfunction "2_P$2") (pintype "passive"))
    )
    (net (code "54") (name "Net-(R23-2)") (class "Default")
      (node (ref "IC3") (pin "8") (pinfunction "8_8") (pintype "passive"))
      (node (ref "R23") (pin "P$2") (pinfunction "2_P$2") (pintype "passive"))
    )
    (net (code "55") (name "Net-(R24-2)") (class "Default")
      (node (ref "IC3") (pin "4") (pinfunction "4_4") (pintype "passive"))
      (node (ref "R24") (pin "P$2") (pinfunction "2_P$2") (pintype "passive"))
    )
    (net (code "56") (name "Net-(R25-2)") (class "Default")
      (node (ref "IC7") (pin "12") (pinfunction "12_12") (pintype "passive"))
      (node (ref "R25") (pin "P$2") (pinfunction "2_P$2") (pintype "passive"))
    )
    (net (code "57") (name "Net-(R26-2)") (class "Default")
      (node (ref "IC7") (pin "8") (pinfunction "8_8") (pintype "passive"))
      (node (ref "R26") (pin "P$2") (pinfunction "2_P$2") (pintype "passive"))
    )
    (net (code "58") (name "Net-(R27-2)") (class "Default")
      (node (ref "IC7") (pin "4") (pinfunction "4_4") (pintype "passive"))
      (node (ref "R27") (pin "P$2") (pinfunction "2_P$2") (pintype "passive"))
    )
    (net (code "59") (name "Net-(R28-2)") (class "Default")
      (node (ref "IC4") (pin "12") (pinfunction "12_12") (pintype "passive"))
      (node (ref "R28") (pin "P$2") (pinfunction "2_P$2") (pintype "passive"))
    )
    (net (code "60") (name "Net-(R29-2)") (class "Default")
      (node (ref "IC4") (pin "8") (pinfunction "8_8") (pintype "passive"))
      (node (ref "R29") (pin "P$2") (pinfunction "2_P$2") (pintype "passive"))
    )
    (net (code "61") (name "Net-(R30-2)") (class "Default")
      (node (ref "IC3") (pin "10") (pinfunction "10_10") (pintype "passive"))
      (node (ref "R30") (pin "P$2") (pinfunction "2_P$2") (pintype "passive"))
    )
    (net (code "62") (name "Net-(R31-2)") (class "Default")
      (node (ref "IC3") (pin "6") (pinfunction "6_6") (pintype "passive"))
      (node (ref "R31") (pin "P$2") (pinfunction "2_P$2") (pintype "passive"))
    )
    (net (code "63") (name "Net-(R32-2)") (class "Default")
      (node (ref "IC3") (pin "2") (pinfunction "2_2") (pintype "passive"))
      (node (ref "R32") (pin "P$2") (pinfunction "2_P$2") (pintype "passive"))
    )
    (net (code "64") (name "Net-(R33-2)") (class "Default")
      (node (ref "IC7") (pin "10") (pinfunction "10_10") (pintype "passive"))
      (node (ref "R33") (pin "P$2") (pinfunction "2_P$2") (pintype "passive"))
    )
    (net (code "65") (name "Net-(R34-2)") (class "Default")
      (node (ref "IC7") (pin "6") (pinfunction "6_6") (pintype "passive"))
      (node (ref "R34") (pin "P$2") (pinfunction "2_P$2") (pintype "passive"))
    )
    (net (code "66") (name "Net-(R35-2)") (class "Default")
      (node (ref "IC7") (pin "2") (pinfunction "2_2") (pintype "passive"))
      (node (ref "R35") (pin "P$2") (pinfunction "2_P$2") (pintype "passive"))
    )
    (net (code "67") (name "Net-(R36-2)") (class "Default")
      (node (ref "IC4") (pin "10") (pinfunction "10_10") (pintype "passive"))
      (node (ref "R36") (pin "P$2") (pinfunction "2_P$2") (pintype "passive"))
    )
    (net (code "68") (name "Net-(R37-2)") (class "Default")
      (node (ref "IC4") (pin "6") (pinfunction "6_6") (pintype "passive"))
      (node (ref "R37") (pin "P$2") (pinfunction "2_P$2") (pintype "passive"))
    )
    (net (code "69") (name "Net-(R39-S)") (class "Default")
      (node (ref "R39") (pin "2") (pinfunction "S_2") (pintype "passive"))
      (node (ref "U$1") (pin "A2") (pinfunction "A2_A2") (pintype "bidirectional"))
    )
    (net (code "70") (name "Net-(S1-2)") (class "Default")
      (node (ref "S1") (pin "3") (pinfunction "2_3") (pintype "passive"))
      (node (ref "U$1") (pin "A0") (pinfunction "A0_A0") (pintype "bidirectional"))
    )
    (net (code "71") (name "Net-(S2-2)") (class "Default")
      (node (ref "S2") (pin "3") (pinfunction "2_3") (pintype "passive"))
      (node (ref "U$1") (pin "A1") (pinfunction "A1_A1") (pintype "bidirectional"))
    )
    (net (code "72") (name "Net-(S3-2)") (class "Default")
      (node (ref "S3") (pin "3") (pinfunction "2_3") (pintype "passive"))
      (node (ref "U$1") (pin "A3") (pinfunction "A3_A3") (pintype "bidirectional"))
    )
    (net (code "73") (name "O1") (class "Default")
      (node (ref "IC1") (pin "2") (pinfunction "OUT2_2") (pintype "output"))
      (node (ref "IC3") (pin "5") (pinfunction "5_5") (pintype "passive"))
      (node (ref "R12") (pin "P$1") (pinfunction "1_P$1") (pintype "passive"))
    )
    (net (code "74") (name "O2") (class "Default")
      (node (ref "IC1") (pin "3") (pinfunction "OUT3_3") (pintype "output"))
      (node (ref "IC3") (pin "3") (pinfunction "3_3") (pintype "passive"))
      (node (ref "R11") (pin "P$1") (pinfunction "1_P$1") (pintype "passive"))
    )
    (net (code "75") (name "O3") (class "Default")
      (node (ref "IC1") (pin "4") (pinfunction "OUT4_4") (pintype "output"))
      (node (ref "IC3") (pin "1") (pinfunction "1_1") (pintype "passive"))
      (node (ref "R10") (pin "P$1") (pinfunction "1_P$1") (pintype "passive"))
    )
    (net (code "76") (name "O4") (class "Default")
      (node (ref "IC1") (pin "5") (pinfunction "OUT5_5") (pintype "output"))
      (node (ref "IC3") (pin "13") (pinfunction "13_13") (pintype "passive"))
      (node (ref "R9") (pin "P$1") (pinfunction "1_P$1") (pintype "passive"))
    )
    (net (code "77") (name "O5") (class "Default")
      (node (ref "IC1") (pin "6") (pinfunction "OUT6_6") (pintype "output"))
      (node (ref "IC3") (pin "11") (pinfunction "11_11") (pintype "passive"))
      (node (ref "R8") (pin "P$1") (pinfunction "1_P$1") (pintype "passive"))
    )
    (net (code "78") (name "O6") (class "Default")
      (node (ref "IC1") (pin "7") (pinfunction "OUT7_7") (pintype "output"))
      (node (ref "IC3") (pin "9") (pinfunction "9_9") (pintype "passive"))
      (node (ref "R7") (pin "P$1") (pinfunction "1_P$1") (pintype "passive"))
    )
    (net (code "79") (name "O7") (class "Default")
      (node (ref "IC1") (pin "8") (pinfunction "OUT8_8") (pintype "output"))
      (node (ref "IC7") (pin "5") (pinfunction "5_5") (pintype "passive"))
      (node (ref "R6") (pin "P$1") (pinfunction "1_P$1") (pintype "passive"))
    )
    (net (code "80") (name "O8") (class "Default")
      (node (ref "IC1") (pin "9") (pinfunction "OUT9_9") (pintype "output"))
      (node (ref "IC7") (pin "3") (pinfunction "3_3") (pintype "passive"))
      (node (ref "R5") (pin "P$1") (pinfunction "1_P$1") (pintype "passive"))
    )
    (net (code "81") (name "O9") (class "Default")
      (node (ref "IC1") (pin "10") (pinfunction "OUT10_10") (pintype "output"))
      (node (ref "IC7") (pin "1") (pinfunction "1_1") (pintype "passive"))
      (node (ref "R4") (pin "P$1") (pinfunction "1_P$1") (pintype "passive"))
    )
    (net (code "82") (name "O10") (class "Default")
      (node (ref "IC1") (pin "11") (pinfunction "OUT11_11") (pintype "output"))
      (node (ref "IC7") (pin "13") (pinfunction "13_13") (pintype "passive"))
      (node (ref "R3") (pin "P$1") (pinfunction "1_P$1") (pintype "passive"))
    )
    (net (code "83") (name "O11") (class "Default")
      (node (ref "IC1") (pin "12") (pinfunction "OUT12_12") (pintype "output"))
      (node (ref "IC7") (pin "11") (pinfunction "11_11") (pintype "passive"))
      (node (ref "R2") (pin "P$1") (pinfunction "1_P$1") (pintype "passive"))
    )
    (net (code "84") (name "O12") (class "Default")
      (node (ref "IC1") (pin "13") (pinfunction "OUT13_13") (pintype "output"))
      (node (ref "IC7") (pin "9") (pinfunction "9_9") (pintype "passive"))
      (node (ref "R13") (pin "P$1") (pinfunction "1_P$1") (pintype "passive"))
    )
    (net (code "85") (name "O13") (class "Default")
      (node (ref "IC1") (pin "14") (pinfunction "OUT14_14") (pintype "output"))
      (node (ref "IC4") (pin "5") (pinfunction "5_5") (pintype "passive"))
      (node (ref "R14") (pin "P$1") (pinfunction "1_P$1") (pintype "passive"))
    )
    (net (code "86") (name "O15") (class "Default")
      (node (ref "IC2") (pin "28") (pinfunction "OUT0_28") (pintype "output"))
      (node (ref "IC4") (pin "1") (pinfunction "1_1") (pintype "passive"))
      (node (ref "R1") (pin "P$1") (pinfunction "1_P$1") (pintype "passive"))
    )
    (net (code "87") (name "O16") (class "Default")
      (node (ref "IC2") (pin "1") (pinfunction "OUT1_1") (pintype "output"))
      (node (ref "IC4") (pin "13") (pinfunction "13_13") (pintype "passive"))
      (node (ref "R16") (pin "P$1") (pinfunction "1_P$1") (pintype "passive"))
    )
    (net (code "88") (name "O17") (class "Default")
      (node (ref "IC2") (pin "2") (pinfunction "OUT2_2") (pintype "output"))
      (node (ref "IC4") (pin "11") (pinfunction "11_11") (pintype "passive"))
      (node (ref "R19") (pin "P$1") (pinfunction "1_P$1") (pintype "passive"))
    )
    (net (code "89") (name "O18") (class "Default")
      (node (ref "IC2") (pin "3") (pinfunction "OUT3_3") (pintype "output"))
      (node (ref "IC4") (pin "9") (pinfunction "9_9") (pintype "passive"))
      (node (ref "R38") (pin "P$1") (pinfunction "1_P$1") (pintype "passive"))
    )
    (net (code "90") (name "T1") (class "Default")
      (node (ref "F8") (pin "2") (pinfunction "D_2") (pintype "bidirectional"))
      (node (ref "X8") (pin "1") (pinfunction "1_1") (pintype "bidirectional"))
    )
    (net (code "91") (name "T2") (class "Default")
      (node (ref "F16") (pin "2") (pinfunction "D_2") (pintype "bidirectional"))
      (node (ref "X16") (pin "1") (pinfunction "1_1") (pintype "bidirectional"))
    )
    (net (code "92") (name "T3") (class "Default")
      (node (ref "F7") (pin "2") (pinfunction "D_2") (pintype "bidirectional"))
      (node (ref "X7") (pin "1") (pinfunction "1_1") (pintype "bidirectional"))
    )
    (net (code "93") (name "T4") (class "Default")
      (node (ref "F18") (pin "2") (pinfunction "D_2") (pintype "bidirectional"))
      (node (ref "X18") (pin "1") (pinfunction "1_1") (pintype "bidirectional"))
    )
    (net (code "94") (name "T5") (class "Default")
      (node (ref "F9") (pin "2") (pinfunction "D_2") (pintype "bidirectional"))
      (node (ref "X9") (pin "1") (pinfunction "1_1") (pintype "bidirectional"))
    )
    (net (code "95") (name "T6") (class "Default")
      (node (ref "F17") (pin "2") (pinfunction "D_2") (pintype "bidirectional"))
      (node (ref "X17") (pin "1") (pinfunction "1_1") (pintype "bidirectional"))
    )
    (net (code "96") (name "T7") (class "Default")
      (node (ref "F5") (pin "2") (pinfunction "D_2") (pintype "bidirectional"))
      (node (ref "X5") (pin "1") (pinfunction "1_1") (pintype "bidirectional"))
    )
    (net (code "97") (name "T8") (class "Default")
      (node (ref "F13") (pin "2") (pinfunction "D_2") (pintype "bidirectional"))
      (node (ref "X13") (pin "1") (pinfunction "1_1") (pintype "bidirectional"))
    )
    (net (code "98") (name "T9") (class "Default")
      (node (ref "F4") (pin "2") (pinfunction "D_2") (pintype "bidirectional"))
      (node (ref "X4") (pin "1") (pinfunction "1_1") (pintype "bidirectional"))
    )
    (net (code "99") (name "T10") (class "Default")
      (node (ref "F15") (pin "2") (pinfunction "D_2") (pintype "bidirectional"))
      (node (ref "X15") (pin "1") (pinfunction "1_1") (pintype "bidirectional"))
    )
    (net (code "100") (name "T11") (class "Default")
      (node (ref "F6") (pin "2") (pinfunction "D_2") (pintype "bidirectional"))
      (node (ref "X6") (pin "1") (pinfunction "1_1") (pintype "bidirectional"))
    )
    (net (code "101") (name "T12") (class "Default")
      (node (ref "F14") (pin "2") (pinfunction "D_2") (pintype "bidirectional"))
      (node (ref "X14") (pin "1") (pinfunction "1_1") (pintype "bidirectional"))
    )
    (net (code "102") (name "T13") (class "Default")
      (node (ref "F2") (pin "2") (pinfunction "D_2") (pintype "bidirectional"))
      (node (ref "X2") (pin "1") (pinfunction "1_1") (pintype "bidirectional"))
    )
    (net (code "103") (name "T14") (class "Default")
      (node (ref "F10") (pin "2") (pinfunction "D_2") (pintype "bidirectional"))
      (node (ref "X10") (pin "1") (pinfunction "1_1") (pintype "bidirectional"))
    )
    (net (code "104") (name "T15") (class "Default")
      (node (ref "F1") (pin "2") (pinfunction "D_2") (pintype "bidirectional"))
      (node (ref "X1") (pin "1") (pinfunction "1_1") (pintype "bidirectional"))
    )
    (net (code "105") (name "T16") (class "Default")
      (node (ref "F12") (pin "2") (pinfunction "D_2") (pintype "bidirectional"))
      (node (ref "X12") (pin "1") (pinfunction "1_1") (pintype "bidirectional"))
    )
    (net (code "106") (name "T17") (class "Default")
      (node (ref "F3") (pin "2") (pinfunction "D_2") (pintype "bidirectional"))
      (node (ref "X3") (pin "1") (pinfunction "1_1") (pintype "bidirectional"))
    )
    (net (code "107") (name "T18") (class "Default")
      (node (ref "F11") (pin "2") (pinfunction "D_2") (pintype "bidirectional"))
      (node (ref "X11") (pin "1") (pinfunction "1_1") (pintype "bidirectional"))
    )
    (net (code "108") (name "VIA6") (class "Default")
      (node (ref "IC1") (pin "15") (pinfunction "OUT15_15") (pintype "output"))
      (node (ref "IC4") (pin "3") (pinfunction "3_3") (pintype "passive"))
      (node (ref "R15") (pin "P$1") (pinfunction "1_P$1") (pintype "passive"))
    )
    (net (code "109") (name "unconnected-(IC1-OUT0-Pad28)") (class "Default")
      (node (ref "IC1") (pin "28") (pinfunction "OUT0_28") (pintype "output"))
    )
    (net (code "110") (name "unconnected-(IC1-OUT1-Pad1)") (class "Default")
      (node (ref "IC1") (pin "1") (pinfunction "OUT1_1") (pintype "output"))
    )
    (net (code "111") (name "unconnected-(IC1-XERR-Pad16)") (class "Default")
      (node (ref "IC1") (pin "16") (pinfunction "XERR_16") (pintype "output"))
    )
    (net (code "112") (name "unconnected-(IC2-OUT14-Pad14)") (class "Default")
      (node (ref "IC2") (pin "14") (pinfunction "OUT14_14") (pintype "output"))
    )
    (net (code "113") (name "unconnected-(IC2-OUT15-Pad15)") (class "Default")
      (node (ref "IC2") (pin "15") (pinfunction "OUT15_15") (pintype "output"))
    )
    (net (code "114") (name "unconnected-(IC2-SOUT-Pad17)") (class "Default")
      (node (ref "IC2") (pin "17") (pinfunction "SOUT_17") (pintype "output"))
    )
    (net (code "115") (name "unconnected-(IC2-XERR-Pad16)") (class "Default")
      (node (ref "IC2") (pin "16") (pinfunction "XERR_16") (pintype "output"))
    )
    (net (code "116") (name "unconnected-(U$1-Pad3.3V)") (class "Default")
      (node (ref "U$1") (pin "3.3V") (pinfunction "3.3V_3.3V") (pintype "bidirectional"))
    )
    (net (code "117") (name "unconnected-(U$1-PadA6)") (class "Default")
      (node (ref "U$1") (pin "A6") (pinfunction "A6_A6") (pintype "bidirectional"))
    )
    (net (code "118") (name "unconnected-(U$1-PadA7)") (class "Default")
      (node (ref "U$1") (pin "A7") (pinfunction "A7_A7") (pintype "bidirectional"))
    )
    (net (code "119") (name "unconnected-(U$1-PadAREF)") (class "Default")
      (node (ref "U$1") (pin "AREF") (pinfunction "AREF_AREF") (pintype "bidirectional"))
    )
    (net (code "120") (name "unconnected-(U$1-PadD2)") (class "Default")
      (node (ref "U$1") (pin "D2") (pinfunction "D2_D2") (pintype "bidirectional"))
    )
    (net (code "121") (name "unconnected-(U$1-PadD12)") (class "Default")
      (node (ref "U$1") (pin "D12") (pinfunction "D12_D12") (pintype "bidirectional"))
    )
    (net (code "122") (name "unconnected-(U$1-PadICSP1)") (class "Default")
      (node (ref "U$1") (pin "ICSP1") (pinfunction "ICSP1_ICSP1") (pintype "bidirectional"))
    )
    (net (code "123") (name "unconnected-(U$1-PadICSP2)") (class "Default")
      (node (ref "U$1") (pin "ICSP2") (pinfunction "ICSP2_ICSP2") (pintype "bidirectional"))
    )
    (net (code "124") (name "unconnected-(U$1-PadICSP3)") (class "Default")
      (node (ref "U$1") (pin "ICSP3") (pinfunction "ICSP3_ICSP3") (pintype "bidirectional"))
    )
    (net (code "125") (name "unconnected-(U$1-PadICSP4)") (class "Default")
      (node (ref "U$1") (pin "ICSP4") (pinfunction "ICSP4_ICSP4") (pintype "bidirectional"))
    )
    (net (code "126") (name "unconnected-(U$1-PadICSP5)") (class "Default")
      (node (ref "U$1") (pin "ICSP5") (pinfunction "ICSP5_ICSP5") (pintype "bidirectional"))
    )
    (net (code "127") (name "unconnected-(U$1-PadICSP6)") (class "Default")
      (node (ref "U$1") (pin "ICSP6") (pinfunction "ICSP6_ICSP6") (pintype "bidirectional"))
    )
    (net (code "128") (name "unconnected-(U$1-PadRST)") (class "Default")
      (node (ref "U$1") (pin "RST") (pinfunction "RST_RST") (pintype "bidirectional"))
    )
    (net (code "129") (name "unconnected-(U$1-PadRST1)") (class "Default")
      (node (ref "U$1") (pin "RST1") (pinfunction "RST1_RST1") (pintype "bidirectional"))
    )
    (net (code "130") (name "unconnected-(U$1-PadRX1)") (class "Default")
      (node (ref "U$1") (pin "RX1") (pinfunction "RX1_RX1") (pintype "bidirectional"))
    )
    (net (code "131") (name "unconnected-(U$1-PadTX0)") (class "Default")
      (node (ref "U$1") (pin "TX0") (pinfunction "TX0_TX0") (pintype "bidirectional"))
    )
  )
)
